# ProPrj___2025-12-14-16-06-23.net
KiCad netlist of a schematic drawn in EasyEDA Pro
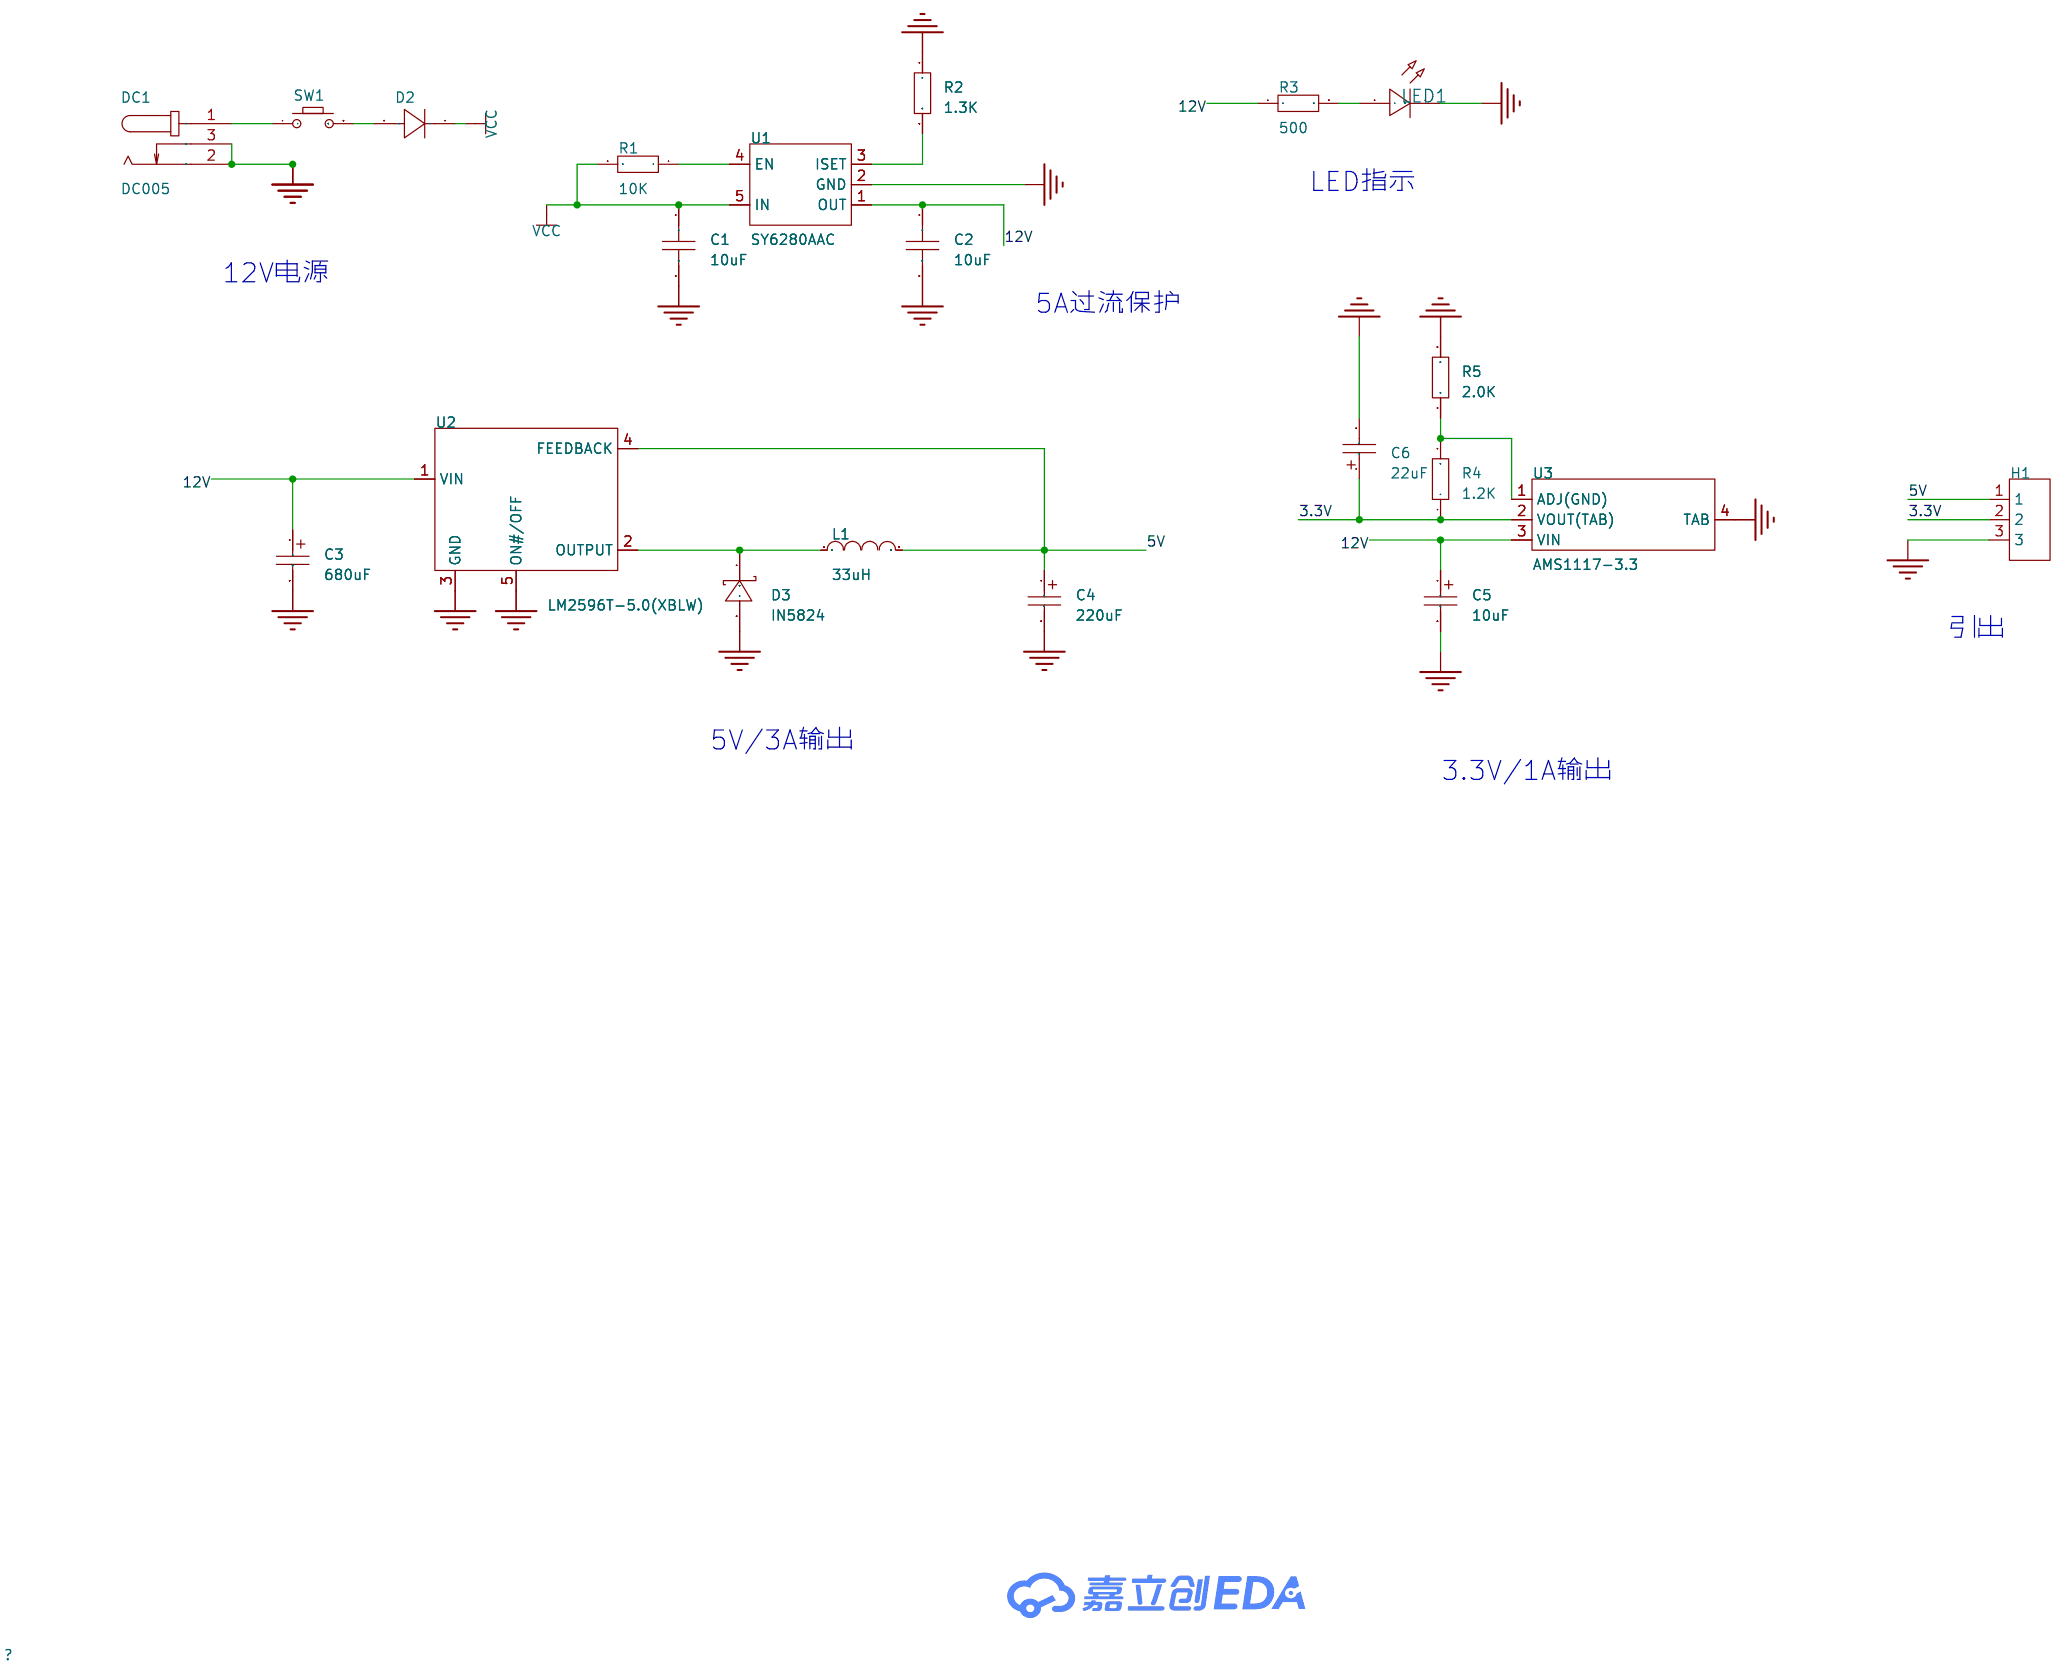
[diagram p0: schematic sheet]

(export (version "E")
  (design (tool "Eeschema 10.0.6"))
  (components
    (comp (ref "C1")
      (value "10uF")
      (footprint "easyedapro:C0603")
      (libsource (lib "easyedapro") (part "Capacitance"))
    )
    (comp (ref "C2")
      (value "10uF")
      (footprint "easyedapro:C0603")
      (libsource (lib "easyedapro") (part "Capacitance"))
    )
    (comp (ref "C3")
      (value "680uF")
      (footprint "easyedapro:C_Ele_SMD_3x5.4mm")
      (libsource (lib "easyedapro") (part "CAP"))
    )
    (comp (ref "C4")
      (value "220uF")
      (footprint "easyedapro:C_Ele_SMD_3x5.4mm")
      (libsource (lib "easyedapro") (part "CAP"))
    )
    (comp (ref "C5")
      (value "10uF")
      (footprint "easyedapro:C_Ele_SMD_3x5.4mm")
      (libsource (lib "easyedapro") (part "CAP"))
    )
    (comp (ref "C6")
      (value "22uF")
      (footprint "easyedapro:C_Ele_SMD_3x5.4mm")
      (libsource (lib "easyedapro") (part "CAP"))
    )
    (comp (ref "D2")
      (value "~")
      (footprint "easyedapro:DO_1N4007")
      (libsource (lib "easyedapro") (part "D_1N4007"))
    )
    (comp (ref "D3")
      (value "IN5824")
      (footprint "easyedapro:SMAF_L3.5-W2.6-LS4.7-RD")
      (libsource (lib "easyedapro") (part "IN5824"))
    )
    (comp (ref "DC1")
      (value "DC005")
      (footprint "easyedapro:DC-IN-TH_DC005")
      (description "连接器类型:DC电源插座;安装方式:弯插;触点内径:2mm;触点外径:6.3mm;额定电流:500mA;额定电压:12V;工作温度:-30°C~+70°C;")
      (fields (field (name "Manufacturer") "SHOU HAN(首韩)"))
      (libsource (lib "easyedapro") (part "DC005_C431533"))
    )
    (comp (ref "H1")
      (value "~")
      (footprint "easyedapro:HDR-TH_3P-P2.54-V-F")
      (libsource (lib "easyedapro") (part "PM254V-11-03-H85"))
    )
    (comp (ref "L1")
      (value "33uH")
      (footprint "easyedapro:L0603")
      (libsource (lib "easyedapro") (part "SDFL1608S100KTF"))
    )
    (comp (ref "LED1")
      (value "~")
      (footprint "easyedapro:LED_0603")
      (libsource (lib "easyedapro") (part "LED_R"))
    )
    (comp (ref "R1") (value "10K") (footprint "easyedapro:R0603") (libsource (lib "easyedapro") (part "电阻")))
    (comp (ref "R2") (value "1.3K") (footprint "easyedapro:R0603") (libsource (lib "easyedapro") (part "电阻")))
    (comp (ref "R3") (value "500") (footprint "easyedapro:R0603") (libsource (lib "easyedapro") (part "电阻")))
    (comp (ref "R4") (value "1.2K") (footprint "easyedapro:R0603") (libsource (lib "easyedapro") (part "电阻")))
    (comp (ref "R5") (value "2.0K") (footprint "easyedapro:R0603") (libsource (lib "easyedapro") (part "电阻")))
    (comp (ref "SW1")
      (value "~")
      (footprint "easyedapro:Key_TH_3.5x6x4.3")
      (libsource (lib "easyedapro") (part "Key_TH_3.5x6x4.3"))
    )
    (comp (ref "U1")
      (value "SY6280AAC")
      (footprint "easyedapro:SOT-23-5_L3.0-W1.7-P0.95-LS2.8-BR")
      (libsource (lib "easyedapro") (part "SY6280AAC_C9900003867"))
    )
    (comp (ref "U2")
      (value "LM2596T-5.0(XBLW)")
      (footprint "easyedapro:TO-220-5L_L10.2-W4.5-P1.71-L")
      (description "功能类型:降压型;工作电压:6V~40V;输出电压:5V;输出电流:3A;输出类型:固定;")
      (fields (field (name "Manufacturer") "XBLW(芯伯乐)"))
      (libsource (lib "easyedapro") (part "LM2596T-5.0(XBLW)"))
    )
    (comp (ref "U3")
      (value "AMS1117-3.3")
      (footprint "easyedapro:SOT-223-4_L6.5-W3.5-P2.30-LS7.0-BR")
      (description "输出类型:固定;工作电压:12V;输出电压:3.3V;输出电流:1A;电源纹波抑制比(PSRR):60dB@(120Hz);输出极性:正极;")
      (fields (field (name "Manufacturer") "UMW(友台半导体)"))
      (libsource (lib "easyedapro") (part "AMS1117-3.3_C347222"))
    )
  )
  (nets
    (net (code "1") (name "/3.3V") (class "Default")
      (node (ref "C6") (pin "1") (pinfunction "1_1") (pintype "input"))
      (node (ref "H1") (pin "2") (pinfunction "2_2") (pintype "unspecified"))
      (node (ref "R4") (pin "1") (pinfunction "1_1") (pintype "input"))
      (node (ref "U3") (pin "2") (pinfunction "VOUT(TAB)_2") (pintype "unspecified"))
    )
    (net (code "2") (name "/5V") (class "Default")
      (node (ref "C4") (pin "1") (pinfunction "1_1") (pintype "input"))
      (node (ref "H1") (pin "1") (pinfunction "1_1") (pintype "unspecified"))
      (node (ref "L1") (pin "2") (pinfunction "2_2") (pintype "unspecified"))
      (node (ref "U2") (pin "4") (pinfunction "FEEDBACK_4") (pintype "unspecified"))
    )
    (net (code "3") (name "/12V") (class "Default")
      (node (ref "C2") (pin "1") (pinfunction "1_1") (pintype "input"))
      (node (ref "C3") (pin "1") (pinfunction "1_1") (pintype "input"))
      (node (ref "C5") (pin "1") (pinfunction "1_1") (pintype "input"))
      (node (ref "R3") (pin "1") (pinfunction "1_1") (pintype "input"))
      (node (ref "U1") (pin "1") (pinfunction "OUT_1") (pintype "unspecified"))
      (node (ref "U2") (pin "1") (pinfunction "VIN_1") (pintype "unspecified"))
      (node (ref "U3") (pin "3") (pinfunction "VIN_3") (pintype "unspecified"))
    )
    (net (code "4") (name "GND") (class "Default")
      (node (ref "C1") (pin "2") (pinfunction "2_2") (pintype "input"))
      (node (ref "C2") (pin "2") (pinfunction "2_2") (pintype "input"))
      (node (ref "C3") (pin "2") (pinfunction "2_2") (pintype "input"))
      (node (ref "C4") (pin "2") (pinfunction "2_2") (pintype "input"))
      (node (ref "C5") (pin "2") (pinfunction "2_2") (pintype "input"))
      (node (ref "C6") (pin "2") (pinfunction "2_2") (pintype "input"))
      (node (ref "D3") (pin "2") (pinfunction "A_2") (pintype "unspecified"))
      (node (ref "DC1") (pin "2") (pinfunction "2_2") (pintype "unspecified"))
      (node (ref "DC1") (pin "3") (pinfunction "3_3") (pintype "unspecified"))
      (node (ref "H1") (pin "3") (pinfunction "3_3") (pintype "unspecified"))
      (node (ref "LED1") (pin "1") (pinfunction "C_1") (pintype "input"))
      (node (ref "R2") (pin "1") (pinfunction "1_1") (pintype "input"))
      (node (ref "R5") (pin "2") (pinfunction "2_2") (pintype "input"))
      (node (ref "U1") (pin "2") (pinfunction "GND_2") (pintype "unspecified"))
      (node (ref "U2") (pin "3") (pinfunction "GND_3") (pintype "unspecified"))
      (node (ref "U2") (pin "5") (pinfunction "ON#/OFF_5") (pintype "unspecified"))
      (node (ref "U3") (pin "4") (pinfunction "TAB_4") (pintype "unspecified"))
    )
    (net (code "5") (name "Net-(D2-A)") (class "Default")
      (node (ref "D2") (pin "2") (pinfunction "A_2") (pintype "input"))
      (node (ref "SW1") (pin "B") (pinfunction "B_B") (pintype "input"))
    )
    (net (code "6") (name "Net-(D3-C)") (class "Default")
      (node (ref "D3") (pin "1") (pinfunction "C_1") (pintype "unspecified"))
      (node (ref "L1") (pin "1") (pinfunction "1_1") (pintype "unspecified"))
      (node (ref "U2") (pin "2") (pinfunction "OUTPUT_2") (pintype "unspecified"))
    )
    (net (code "7") (name "Net-(DC1-Pad1)") (class "Default")
      (node (ref "DC1") (pin "1") (pinfunction "1_1") (pintype "unspecified"))
      (node (ref "SW1") (pin "A") (pinfunction "A_A") (pintype "input"))
    )
    (net (code "8") (name "Net-(LED1-A)") (class "Default")
      (node (ref "LED1") (pin "2") (pinfunction "A_2") (pintype "input"))
      (node (ref "R3") (pin "2") (pinfunction "2_2") (pintype "input"))
    )
    (net (code "9") (name "Net-(U1-EN)") (class "Default")
      (node (ref "R1") (pin "1") (pinfunction "1_1") (pintype "input"))
      (node (ref "U1") (pin "4") (pinfunction "EN_4") (pintype "unspecified"))
    )
    (net (code "10") (name "Net-(U1-ISET)") (class "Default")
      (node (ref "R2") (pin "2") (pinfunction "2_2") (pintype "input"))
      (node (ref "U1") (pin "3") (pinfunction "ISET_3") (pintype "unspecified"))
    )
    (net (code "11") (name "Net-(U3-ADJ(GND))") (class "Default")
      (node (ref "R4") (pin "2") (pinfunction "2_2") (pintype "input"))
      (node (ref "R5") (pin "1") (pinfunction "1_1") (pintype "input"))
      (node (ref "U3") (pin "1") (pinfunction "ADJ(GND)_1") (pintype "unspecified"))
    )
    (net (code "12") (name "VCC") (class "Default")
      (node (ref "C1") (pin "1") (pinfunction "1_1") (pintype "input"))
      (node (ref "D2") (pin "1") (pinfunction "K_1") (pintype "input"))
      (node (ref "R1") (pin "2") (pinfunction "2_2") (pintype "input"))
      (node (ref "U1") (pin "5") (pinfunction "IN_5") (pintype "unspecified"))
    )
  )
)
